# 100-678-02-00_CIB.net
KiCad netlist of a schematic drawn in Altium Designer
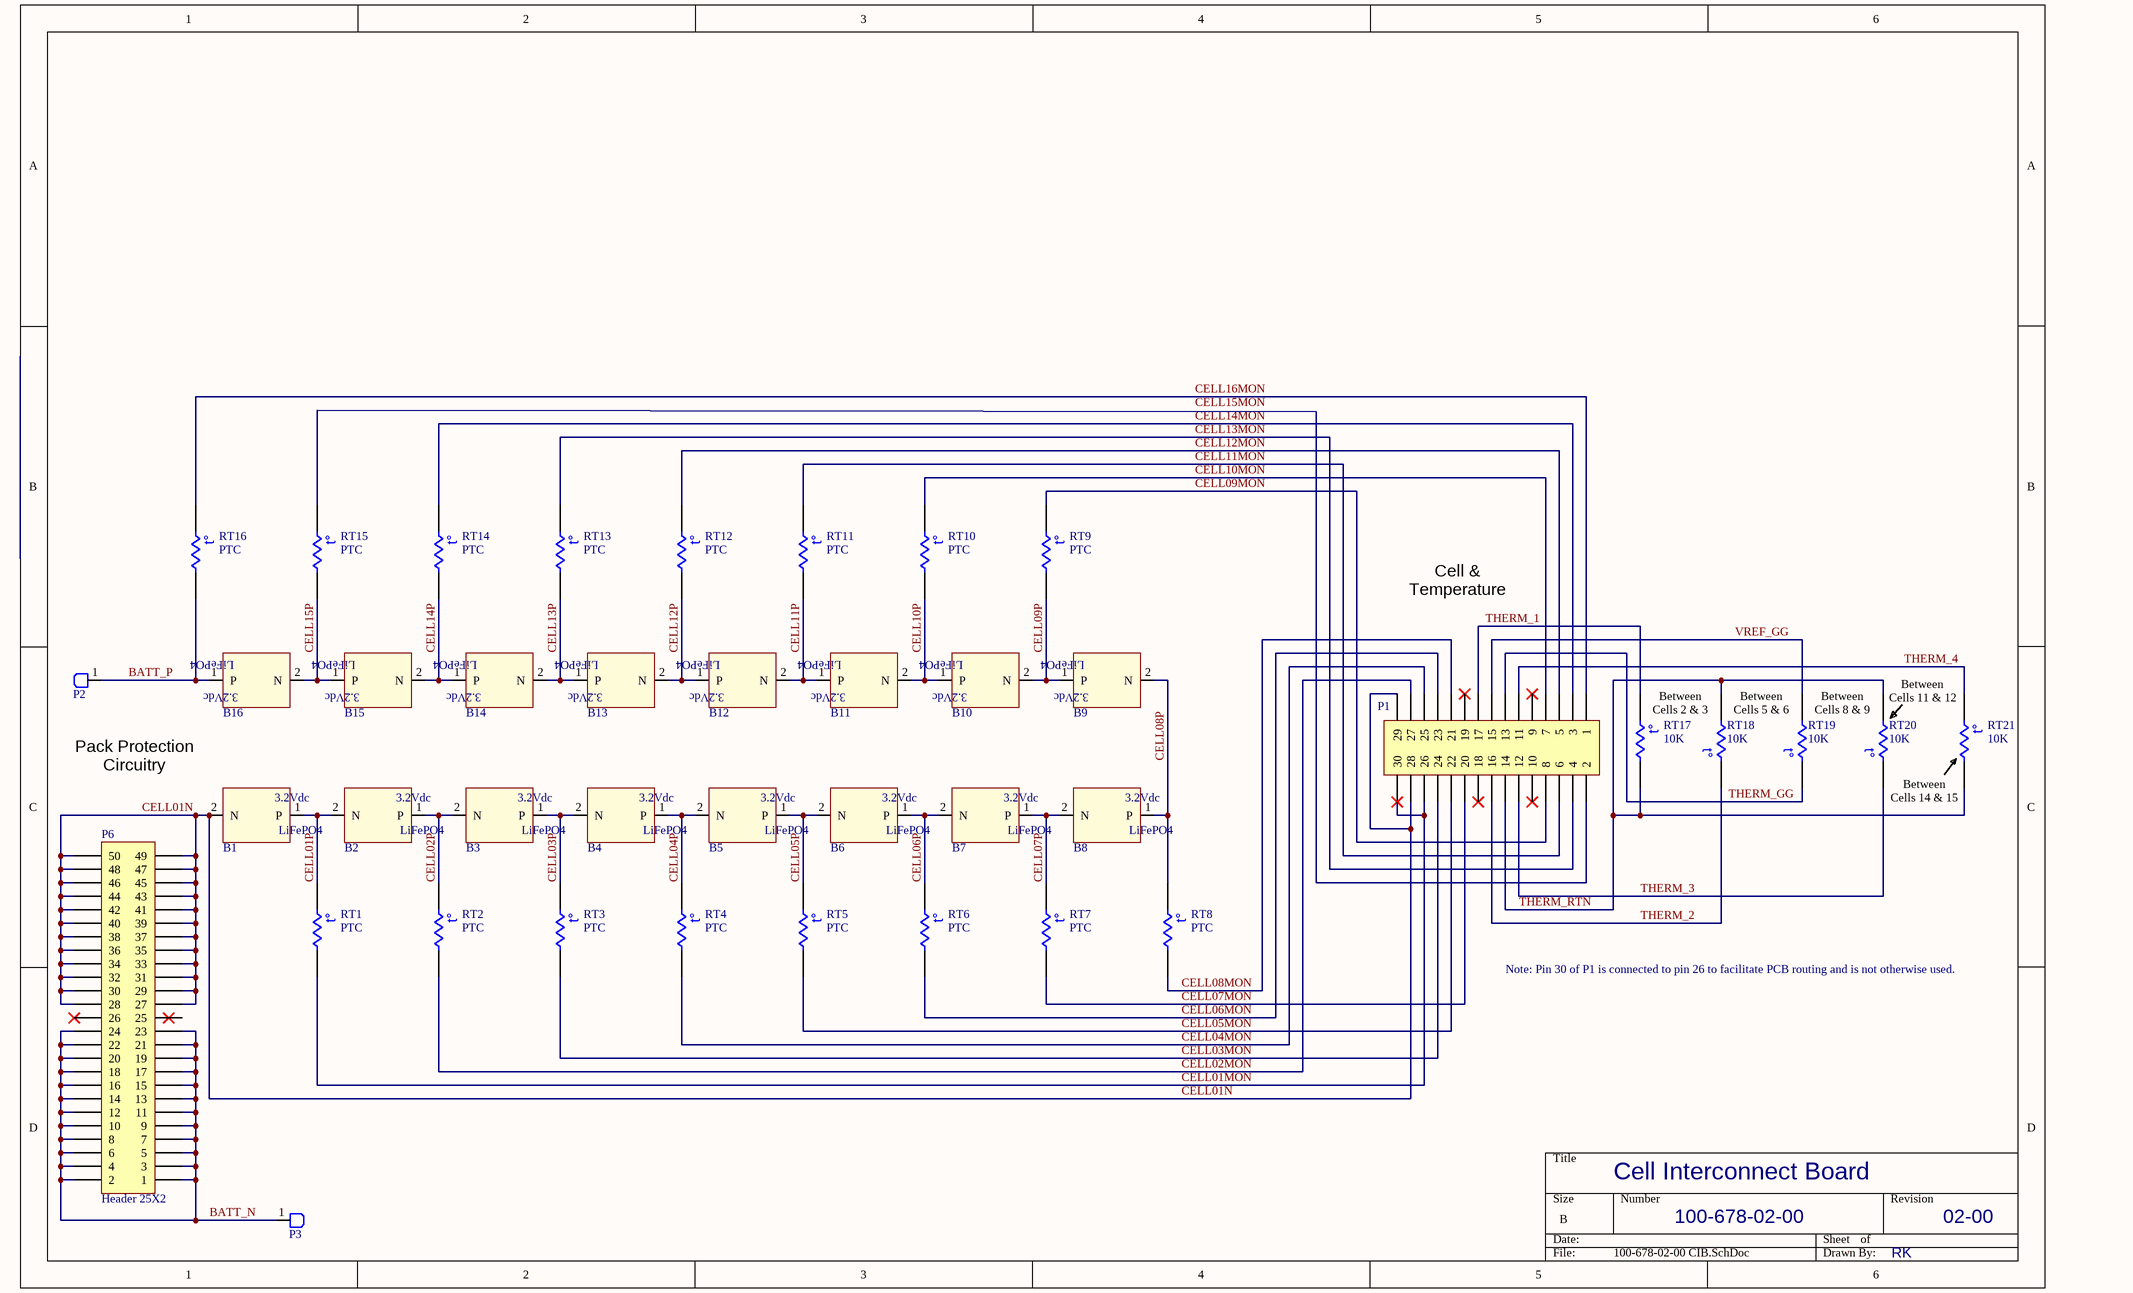
[diagram p0: 100-678-02-00 CIB.SchDoc]

(export (version "E")
  (design (tool "Eeschema 10.0.6"))
  (components
    (comp (ref "B1")
      (value "TENERGY 30209 LiFePO4 Cell")
      (footprint "TENERGY 30209 LiFePO4 Cell")
      (libsource (lib "") (part "TENERGY 30209 LiFePO4 Cell_1"))
    )
    (comp (ref "B2")
      (value "TENERGY 30209 LiFePO4 Cell")
      (footprint "TENERGY 30209 LiFePO4 Cell")
      (libsource (lib "") (part "TENERGY 30209 LiFePO4 Cell_1"))
    )
    (comp (ref "B3")
      (value "TENERGY 30209 LiFePO4 Cell")
      (footprint "TENERGY 30209 LiFePO4 Cell")
      (libsource (lib "") (part "TENERGY 30209 LiFePO4 Cell_1"))
    )
    (comp (ref "B4")
      (value "TENERGY 30209 LiFePO4 Cell")
      (footprint "TENERGY 30209 LiFePO4 Cell")
      (libsource (lib "") (part "TENERGY 30209 LiFePO4 Cell_1"))
    )
    (comp (ref "B5")
      (value "TENERGY 30209 LiFePO4 Cell")
      (footprint "TENERGY 30209 LiFePO4 Cell")
      (libsource (lib "") (part "TENERGY 30209 LiFePO4 Cell_1"))
    )
    (comp (ref "B6")
      (value "TENERGY 30209 LiFePO4 Cell")
      (footprint "TENERGY 30209 LiFePO4 Cell")
      (libsource (lib "") (part "TENERGY 30209 LiFePO4 Cell_1"))
    )
    (comp (ref "B7")
      (value "TENERGY 30209 LiFePO4 Cell")
      (footprint "TENERGY 30209 LiFePO4 Cell")
      (libsource (lib "") (part "TENERGY 30209 LiFePO4 Cell_1"))
    )
    (comp (ref "B8")
      (value "TENERGY 30209 LiFePO4 Cell")
      (footprint "TENERGY 30209 LiFePO4 Cell")
      (libsource (lib "") (part "TENERGY 30209 LiFePO4 Cell_1"))
    )
    (comp (ref "B9")
      (value "TENERGY 30209 LiFePO4 Cell")
      (footprint "TENERGY 30209 LiFePO4 Cell")
      (libsource (lib "STEM_SCH") (part "TENERGY 30209 LiFePO4 Cell"))
    )
    (comp (ref "B10")
      (value "TENERGY 30209 LiFePO4 Cell")
      (footprint "TENERGY 30209 LiFePO4 Cell")
      (libsource (lib "STEM_SCH") (part "TENERGY 30209 LiFePO4 Cell"))
    )
    (comp (ref "B11")
      (value "TENERGY 30209 LiFePO4 Cell")
      (footprint "TENERGY 30209 LiFePO4 Cell")
      (libsource (lib "STEM_SCH") (part "TENERGY 30209 LiFePO4 Cell"))
    )
    (comp (ref "B12")
      (value "TENERGY 30209 LiFePO4 Cell")
      (footprint "TENERGY 30209 LiFePO4 Cell")
      (libsource (lib "STEM_SCH") (part "TENERGY 30209 LiFePO4 Cell"))
    )
    (comp (ref "B13")
      (value "TENERGY 30209 LiFePO4 Cell")
      (footprint "TENERGY 30209 LiFePO4 Cell")
      (libsource (lib "STEM_SCH") (part "TENERGY 30209 LiFePO4 Cell"))
    )
    (comp (ref "B14")
      (value "TENERGY 30209 LiFePO4 Cell")
      (footprint "TENERGY 30209 LiFePO4 Cell")
      (libsource (lib "STEM_SCH") (part "TENERGY 30209 LiFePO4 Cell"))
    )
    (comp (ref "B15")
      (value "TENERGY 30209 LiFePO4 Cell")
      (footprint "TENERGY 30209 LiFePO4 Cell")
      (libsource (lib "STEM_SCH") (part "TENERGY 30209 LiFePO4 Cell"))
    )
    (comp (ref "B16")
      (value "TENERGY 30209 LiFePO4 Cell")
      (footprint "TENERGY 30209 LiFePO4 Cell")
      (libsource (lib "STEM_SCH") (part "TENERGY 30209 LiFePO4 Cell"))
    )
    (comp (ref "P1")
      (value "Header 15X2")
      (footprint "CONN 2X15 SKT TH")
      (description "CONN, SKT, 15 X 2, 0.1\" CTRS, TH, 0.435\" HEIGHT GOLD")
      (fields
        (field (name "MANUFACTURER") "SAMTEC")
        (field (name "MANUFACTURER PART NUMBER") "ESQ-115-13-L-D")
        (field (name "PUBLISHER") "Altium Limited")
      )
      (libsource (lib "Miscellaneous Connectors") (part "Header 15X2"))
    )
    (comp (ref "P2")
      (value "CONN TAB MALE 1/4\" PC TH")
      (footprint "TERM, LUG, RING TONGUE, #8-32 W/ PEM")
      (description "NUT PEM 8-32 0.25\" HOLE")
      (fields
        (field (name "MANUFACTURER") "PennEngineering")
        (field (name "MANUFACTURER PART NUMBER") "KFS2-832")
      )
      (libsource (lib "STEM_SCH") (part "CONN TAB MALE 1/4{dblquote} PC TH"))
    )
    (comp (ref "P3")
      (value "CONN TAB MALE 1/4\" PC TH")
      (footprint "TERM, LUG, RING TONGUE, #8-32 W/ PEM")
      (description "NUT PEM 8-32 0.25\" HOLE")
      (fields
        (field (name "MANUFACTURER") "PennEngineering")
        (field (name "MANUFACTURER PART NUMBER") "KFS2-832")
      )
      (libsource (lib "STEM_SCH") (part "CONN TAB MALE 1/4{dblquote} PC TH"))
    )
    (comp (ref "P6")
      (value "Header 25X2")
      (footprint "CONN 2X25 SKT TH")
      (description "CONN, SKT, 25 X 2, 0.1\" CTRS, TH, 0.435\" HEIGHT GOLD")
      (fields
        (field (name "MANUFACTURER") "SAMTEC")
        (field (name "MANUFACTURER PART NUMBER") "ESQ-125-13-L-D")
        (field (name "PUBLISHER") "Altium Limited")
      )
      (libsource (lib "Miscellaneous Connectors") (part "Header 25X2"))
    )
    (comp (ref "RT1")
      (value "PTC")
      (footprint "THERM 1812")
      (description "PTC 2.00A 8VDC RESETTABLE 1812L")
      (fields
        (field (name "MANUFACTURER") "Littelfuse Inc")
        (field (name "MANUFACTURER PART NUMBER") "1812L200THPR")
      )
      (libsource (lib "Miscellaneous Devices") (part "Res Thermal"))
    )
    (comp (ref "RT2")
      (value "PTC")
      (footprint "THERM 1812")
      (description "PTC 2.00A 8VDC RESETTABLE 1812L")
      (fields
        (field (name "MANUFACTURER") "Littelfuse Inc")
        (field (name "MANUFACTURER PART NUMBER") "1812L200THPR")
      )
      (libsource (lib "Miscellaneous Devices") (part "Res Thermal"))
    )
    (comp (ref "RT3")
      (value "PTC")
      (footprint "THERM 1812")
      (description "PTC 2.00A 8VDC RESETTABLE 1812L")
      (fields
        (field (name "MANUFACTURER") "Littelfuse Inc")
        (field (name "MANUFACTURER PART NUMBER") "1812L200THPR")
      )
      (libsource (lib "Miscellaneous Devices") (part "Res Thermal"))
    )
    (comp (ref "RT4")
      (value "PTC")
      (footprint "THERM 1812")
      (description "PTC 2.00A 8VDC RESETTABLE 1812L")
      (fields
        (field (name "MANUFACTURER") "Littelfuse Inc")
        (field (name "MANUFACTURER PART NUMBER") "1812L200THPR")
      )
      (libsource (lib "Miscellaneous Devices") (part "Res Thermal"))
    )
    (comp (ref "RT5")
      (value "PTC")
      (footprint "THERM 1812")
      (description "PTC 2.00A 8VDC RESETTABLE 1812L")
      (fields
        (field (name "MANUFACTURER") "Littelfuse Inc")
        (field (name "MANUFACTURER PART NUMBER") "1812L200THPR")
      )
      (libsource (lib "Miscellaneous Devices") (part "Res Thermal"))
    )
    (comp (ref "RT6")
      (value "PTC")
      (footprint "THERM 1812")
      (description "PTC 2.00A 8VDC RESETTABLE 1812L")
      (fields
        (field (name "MANUFACTURER") "Littelfuse Inc")
        (field (name "MANUFACTURER PART NUMBER") "1812L200THPR")
      )
      (libsource (lib "Miscellaneous Devices") (part "Res Thermal"))
    )
    (comp (ref "RT7")
      (value "PTC")
      (footprint "THERM 1812")
      (description "PTC 2.00A 8VDC RESETTABLE 1812L")
      (fields
        (field (name "MANUFACTURER") "Littelfuse Inc")
        (field (name "MANUFACTURER PART NUMBER") "1812L200THPR")
      )
      (libsource (lib "Miscellaneous Devices") (part "Res Thermal"))
    )
    (comp (ref "RT8")
      (value "PTC")
      (footprint "THERM 1812")
      (description "PTC 2.00A 8VDC RESETTABLE 1812L")
      (fields
        (field (name "MANUFACTURER") "Littelfuse Inc")
        (field (name "MANUFACTURER PART NUMBER") "1812L200THPR")
      )
      (libsource (lib "Miscellaneous Devices") (part "Res Thermal"))
    )
    (comp (ref "RT9")
      (value "PTC")
      (footprint "THERM 1812")
      (description "PTC 2.00A 8VDC RESETTABLE 1812L")
      (fields
        (field (name "MANUFACTURER") "Littelfuse Inc")
        (field (name "MANUFACTURER PART NUMBER") "1812L200THPR")
      )
      (libsource (lib "Miscellaneous Devices") (part "Res Thermal"))
    )
    (comp (ref "RT10")
      (value "PTC")
      (footprint "THERM 1812")
      (description "PTC 2.00A 8VDC RESETTABLE 1812L")
      (fields
        (field (name "MANUFACTURER") "Littelfuse Inc")
        (field (name "MANUFACTURER PART NUMBER") "1812L200THPR")
      )
      (libsource (lib "Miscellaneous Devices") (part "Res Thermal"))
    )
    (comp (ref "RT11")
      (value "PTC")
      (footprint "THERM 1812")
      (description "PTC 2.00A 8VDC RESETTABLE 1812L")
      (fields
        (field (name "MANUFACTURER") "Littelfuse Inc")
        (field (name "MANUFACTURER PART NUMBER") "1812L200THPR")
      )
      (libsource (lib "Miscellaneous Devices") (part "Res Thermal"))
    )
    (comp (ref "RT12")
      (value "PTC")
      (footprint "THERM 1812")
      (description "PTC 2.00A 8VDC RESETTABLE 1812L")
      (fields
        (field (name "MANUFACTURER") "Littelfuse Inc")
        (field (name "MANUFACTURER PART NUMBER") "1812L200THPR")
      )
      (libsource (lib "Miscellaneous Devices") (part "Res Thermal"))
    )
    (comp (ref "RT13")
      (value "PTC")
      (footprint "THERM 1812")
      (description "PTC 2.00A 8VDC RESETTABLE 1812L")
      (fields
        (field (name "MANUFACTURER") "Littelfuse Inc")
        (field (name "MANUFACTURER PART NUMBER") "1812L200THPR")
      )
      (libsource (lib "Miscellaneous Devices") (part "Res Thermal"))
    )
    (comp (ref "RT14")
      (value "PTC")
      (footprint "THERM 1812")
      (description "PTC 2.00A 8VDC RESETTABLE 1812L")
      (fields
        (field (name "MANUFACTURER") "Littelfuse Inc")
        (field (name "MANUFACTURER PART NUMBER") "1812L200THPR")
      )
      (libsource (lib "Miscellaneous Devices") (part "Res Thermal"))
    )
    (comp (ref "RT15")
      (value "PTC")
      (footprint "THERM 1812")
      (description "PTC 2.00A 8VDC RESETTABLE 1812L")
      (fields
        (field (name "MANUFACTURER") "Littelfuse Inc")
        (field (name "MANUFACTURER PART NUMBER") "1812L200THPR")
      )
      (libsource (lib "Miscellaneous Devices") (part "Res Thermal"))
    )
    (comp (ref "RT16")
      (value "PTC")
      (footprint "THERM 1812")
      (description "PTC 2.00A 8VDC RESETTABLE 1812L")
      (fields
        (field (name "MANUFACTURER") "Littelfuse Inc")
        (field (name "MANUFACTURER PART NUMBER") "1812L200THPR")
      )
      (libsource (lib "Miscellaneous Devices") (part "Res Thermal"))
    )
    (comp (ref "RT17")
      (value "10K")
      (footprint "THERMISTOR JT")
      (description "THERMISTOR NTC 10K B3435 TF 100MM")
      (fields (field (name "MANUFACTURER PART NUMBER") "103JT-100") (field (name "MANUFACTURER") "Semitec"))
      (libsource (lib "Miscellaneous Devices") (part "Res Thermal"))
    )
    (comp (ref "RT18")
      (value "10K")
      (footprint "THERMISTOR JT")
      (description "THERMISTOR NTC 10K B3435 TF 100MM")
      (fields (field (name "MANUFACTURER PART NUMBER") "103JT-100") (field (name "MANUFACTURER") "Semitec"))
      (libsource (lib "Miscellaneous Devices") (part "Res Thermal"))
    )
    (comp (ref "RT19")
      (value "10K")
      (footprint "THERMISTOR JT")
      (description "THERMISTOR NTC 10K B3435 TF 100MM")
      (fields (field (name "MANUFACTURER PART NUMBER") "103JT-100") (field (name "MANUFACTURER") "Semitec"))
      (libsource (lib "Miscellaneous Devices") (part "Res Thermal"))
    )
    (comp (ref "RT20")
      (value "10K")
      (footprint "THERMISTOR JT")
      (description "THERMISTOR NTC 10K B3435 TF 100MM")
      (fields (field (name "MANUFACTURER PART NUMBER") "103JT-100") (field (name "MANUFACTURER") "Semitec"))
      (libsource (lib "Miscellaneous Devices") (part "Res Thermal"))
    )
    (comp (ref "RT21")
      (value "10K")
      (footprint "THERMISTOR JT")
      (description "THERMISTOR NTC 10K B3435 TF 100MM")
      (fields (field (name "MANUFACTURER PART NUMBER") "103JT-100") (field (name "MANUFACTURER") "Semitec"))
      (libsource (lib "Miscellaneous Devices") (part "Res Thermal"))
    )
  )
  (nets
    (net (code "1") (name "/BATT_N") (class "Default")
      (node (ref "P3") (pin "1") (pinfunction "1_1") (pintype "passive"))
      (node (ref "P6") (pin "1") (pinfunction "1_1") (pintype "passive"))
      (node (ref "P6") (pin "10") (pinfunction "10_10") (pintype "passive"))
      (node (ref "P6") (pin "11") (pinfunction "11_11") (pintype "passive"))
      (node (ref "P6") (pin "12") (pinfunction "12_12") (pintype "passive"))
      (node (ref "P6") (pin "13") (pinfunction "13_13") (pintype "passive"))
      (node (ref "P6") (pin "14") (pinfunction "14_14") (pintype "passive"))
      (node (ref "P6") (pin "15") (pinfunction "15_15") (pintype "passive"))
      (node (ref "P6") (pin "16") (pinfunction "16_16") (pintype "passive"))
      (node (ref "P6") (pin "17") (pinfunction "17_17") (pintype "passive"))
      (node (ref "P6") (pin "18") (pinfunction "18_18") (pintype "passive"))
      (node (ref "P6") (pin "19") (pinfunction "19_19") (pintype "passive"))
      (node (ref "P6") (pin "2") (pinfunction "2_2") (pintype "passive"))
      (node (ref "P6") (pin "20") (pinfunction "20_20") (pintype "passive"))
      (node (ref "P6") (pin "21") (pinfunction "21_21") (pintype "passive"))
      (node (ref "P6") (pin "22") (pinfunction "22_22") (pintype "passive"))
      (node (ref "P6") (pin "23") (pinfunction "23_23") (pintype "passive"))
      (node (ref "P6") (pin "24") (pinfunction "24_24") (pintype "passive"))
      (node (ref "P6") (pin "3") (pinfunction "3_3") (pintype "passive"))
      (node (ref "P6") (pin "4") (pinfunction "4_4") (pintype "passive"))
      (node (ref "P6") (pin "5") (pinfunction "5_5") (pintype "passive"))
      (node (ref "P6") (pin "6") (pinfunction "6_6") (pintype "passive"))
      (node (ref "P6") (pin "7") (pinfunction "7_7") (pintype "passive"))
      (node (ref "P6") (pin "8") (pinfunction "8_8") (pintype "passive"))
      (node (ref "P6") (pin "9") (pinfunction "9_9") (pintype "passive"))
    )
    (net (code "2") (name "/BATT_P") (class "Default")
      (node (ref "B16") (pin "1") (pinfunction "P_1") (pintype "passive"))
      (node (ref "P2") (pin "1") (pinfunction "1_1") (pintype "passive"))
      (node (ref "RT16") (pin "2") (pinfunction "2_2") (pintype "passive"))
    )
    (net (code "3") (name "/CELL01MON") (class "Default")
      (node (ref "P1") (pin "26") (pinfunction "26_26") (pintype "passive"))
      (node (ref "P1") (pin "30") (pinfunction "30_30") (pintype "passive"))
      (node (ref "RT1") (pin "2") (pinfunction "2_2") (pintype "passive"))
    )
    (net (code "4") (name "/CELL01N") (class "Default")
      (node (ref "B1") (pin "2") (pinfunction "N_2") (pintype "passive"))
      (node (ref "P1") (pin "28") (pinfunction "28_28") (pintype "passive"))
      (node (ref "P1") (pin "29") (pinfunction "29_29") (pintype "passive"))
      (node (ref "P6") (pin "27") (pinfunction "27_27") (pintype "passive"))
      (node (ref "P6") (pin "28") (pinfunction "28_28") (pintype "passive"))
      (node (ref "P6") (pin "29") (pinfunction "29_29") (pintype "passive"))
      (node (ref "P6") (pin "30") (pinfunction "30_30") (pintype "passive"))
      (node (ref "P6") (pin "31") (pinfunction "31_31") (pintype "passive"))
      (node (ref "P6") (pin "32") (pinfunction "32_32") (pintype "passive"))
      (node (ref "P6") (pin "33") (pinfunction "33_33") (pintype "passive"))
      (node (ref "P6") (pin "34") (pinfunction "34_34") (pintype "passive"))
      (node (ref "P6") (pin "35") (pinfunction "35_35") (pintype "passive"))
      (node (ref "P6") (pin "36") (pinfunction "36_36") (pintype "passive"))
      (node (ref "P6") (pin "37") (pinfunction "37_37") (pintype "passive"))
      (node (ref "P6") (pin "38") (pinfunction "38_38") (pintype "passive"))
      (node (ref "P6") (pin "39") (pinfunction "39_39") (pintype "passive"))
      (node (ref "P6") (pin "40") (pinfunction "40_40") (pintype "passive"))
      (node (ref "P6") (pin "41") (pinfunction "41_41") (pintype "passive"))
      (node (ref "P6") (pin "42") (pinfunction "42_42") (pintype "passive"))
      (node (ref "P6") (pin "43") (pinfunction "43_43") (pintype "passive"))
      (node (ref "P6") (pin "44") (pinfunction "44_44") (pintype "passive"))
      (node (ref "P6") (pin "45") (pinfunction "45_45") (pintype "passive"))
      (node (ref "P6") (pin "46") (pinfunction "46_46") (pintype "passive"))
      (node (ref "P6") (pin "47") (pinfunction "47_47") (pintype "passive"))
      (node (ref "P6") (pin "48") (pinfunction "48_48") (pintype "passive"))
      (node (ref "P6") (pin "49") (pinfunction "49_49") (pintype "passive"))
      (node (ref "P6") (pin "50") (pinfunction "50_50") (pintype "passive"))
    )
    (net (code "5") (name "/CELL01P") (class "Default")
      (node (ref "B1") (pin "1") (pinfunction "P_1") (pintype "passive"))
      (node (ref "B2") (pin "2") (pinfunction "N_2") (pintype "passive"))
      (node (ref "RT1") (pin "1") (pinfunction "1_1") (pintype "passive"))
    )
    (net (code "6") (name "/CELL02MON") (class "Default")
      (node (ref "P1") (pin "27") (pinfunction "27_27") (pintype "passive"))
      (node (ref "RT2") (pin "2") (pinfunction "2_2") (pintype "passive"))
    )
    (net (code "7") (name "/CELL02P") (class "Default")
      (node (ref "B2") (pin "1") (pinfunction "P_1") (pintype "passive"))
      (node (ref "B3") (pin "2") (pinfunction "N_2") (pintype "passive"))
      (node (ref "RT2") (pin "1") (pinfunction "1_1") (pintype "passive"))
    )
    (net (code "8") (name "/CELL03MON") (class "Default")
      (node (ref "P1") (pin "24") (pinfunction "24_24") (pintype "passive"))
      (node (ref "RT3") (pin "2") (pinfunction "2_2") (pintype "passive"))
    )
    (net (code "9") (name "/CELL03P") (class "Default")
      (node (ref "B3") (pin "1") (pinfunction "P_1") (pintype "passive"))
      (node (ref "B4") (pin "2") (pinfunction "N_2") (pintype "passive"))
      (node (ref "RT3") (pin "1") (pinfunction "1_1") (pintype "passive"))
    )
    (net (code "10") (name "/CELL04MON") (class "Default")
      (node (ref "P1") (pin "25") (pinfunction "25_25") (pintype "passive"))
      (node (ref "RT4") (pin "2") (pinfunction "2_2") (pintype "passive"))
    )
    (net (code "11") (name "/CELL04P") (class "Default")
      (node (ref "B4") (pin "1") (pinfunction "P_1") (pintype "passive"))
      (node (ref "B5") (pin "2") (pinfunction "N_2") (pintype "passive"))
      (node (ref "RT4") (pin "1") (pinfunction "1_1") (pintype "passive"))
    )
    (net (code "12") (name "/CELL05MON") (class "Default")
      (node (ref "P1") (pin "22") (pinfunction "22_22") (pintype "passive"))
      (node (ref "RT5") (pin "2") (pinfunction "2_2") (pintype "passive"))
    )
    (net (code "13") (name "/CELL05P") (class "Default")
      (node (ref "B5") (pin "1") (pinfunction "P_1") (pintype "passive"))
      (node (ref "B6") (pin "2") (pinfunction "N_2") (pintype "passive"))
      (node (ref "RT5") (pin "1") (pinfunction "1_1") (pintype "passive"))
    )
    (net (code "14") (name "/CELL06MON") (class "Default")
      (node (ref "P1") (pin "23") (pinfunction "23_23") (pintype "passive"))
      (node (ref "RT6") (pin "2") (pinfunction "2_2") (pintype "passive"))
    )
    (net (code "15") (name "/CELL06P") (class "Default")
      (node (ref "B6") (pin "1") (pinfunction "P_1") (pintype "passive"))
      (node (ref "B7") (pin "2") (pinfunction "N_2") (pintype "passive"))
      (node (ref "RT6") (pin "1") (pinfunction "1_1") (pintype "passive"))
    )
    (net (code "16") (name "/CELL07MON") (class "Default")
      (node (ref "P1") (pin "20") (pinfunction "20_20") (pintype "passive"))
      (node (ref "RT7") (pin "2") (pinfunction "2_2") (pintype "passive"))
    )
    (net (code "17") (name "/CELL07P") (class "Default")
      (node (ref "B7") (pin "1") (pinfunction "P_1") (pintype "passive"))
      (node (ref "B8") (pin "2") (pinfunction "N_2") (pintype "passive"))
      (node (ref "RT7") (pin "1") (pinfunction "1_1") (pintype "passive"))
    )
    (net (code "18") (name "/CELL08MON") (class "Default")
      (node (ref "P1") (pin "21") (pinfunction "21_21") (pintype "passive"))
      (node (ref "RT8") (pin "2") (pinfunction "2_2") (pintype "passive"))
    )
    (net (code "19") (name "/CELL08P") (class "Default")
      (node (ref "B8") (pin "1") (pinfunction "P_1") (pintype "passive"))
      (node (ref "B9") (pin "2") (pinfunction "N_2") (pintype "passive"))
      (node (ref "RT8") (pin "1") (pinfunction "1_1") (pintype "passive"))
    )
    (net (code "20") (name "/CELL09MON") (class "Default")
      (node (ref "P1") (pin "8") (pinfunction "8_8") (pintype "passive"))
      (node (ref "RT9") (pin "1") (pinfunction "1_1") (pintype "passive"))
    )
    (net (code "21") (name "/CELL09P") (class "Default")
      (node (ref "B10") (pin "2") (pinfunction "N_2") (pintype "passive"))
      (node (ref "B9") (pin "1") (pinfunction "P_1") (pintype "passive"))
      (node (ref "RT9") (pin "2") (pinfunction "2_2") (pintype "passive"))
    )
    (net (code "22") (name "/CELL10MON") (class "Default")
      (node (ref "P1") (pin "7") (pinfunction "7_7") (pintype "passive"))
      (node (ref "RT10") (pin "1") (pinfunction "1_1") (pintype "passive"))
    )
    (net (code "23") (name "/CELL10P") (class "Default")
      (node (ref "B10") (pin "1") (pinfunction "P_1") (pintype "passive"))
      (node (ref "B11") (pin "2") (pinfunction "N_2") (pintype "passive"))
      (node (ref "RT10") (pin "2") (pinfunction "2_2") (pintype "passive"))
    )
    (net (code "24") (name "/CELL11MON") (class "Default")
      (node (ref "P1") (pin "6") (pinfunction "6_6") (pintype "passive"))
      (node (ref "RT11") (pin "1") (pinfunction "1_1") (pintype "passive"))
    )
    (net (code "25") (name "/CELL11P") (class "Default")
      (node (ref "B11") (pin "1") (pinfunction "P_1") (pintype "passive"))
      (node (ref "B12") (pin "2") (pinfunction "N_2") (pintype "passive"))
      (node (ref "RT11") (pin "2") (pinfunction "2_2") (pintype "passive"))
    )
    (net (code "26") (name "/CELL12MON") (class "Default")
      (node (ref "P1") (pin "5") (pinfunction "5_5") (pintype "passive"))
      (node (ref "RT12") (pin "1") (pinfunction "1_1") (pintype "passive"))
    )
    (net (code "27") (name "/CELL12P") (class "Default")
      (node (ref "B12") (pin "1") (pinfunction "P_1") (pintype "passive"))
      (node (ref "B13") (pin "2") (pinfunction "N_2") (pintype "passive"))
      (node (ref "RT12") (pin "2") (pinfunction "2_2") (pintype "passive"))
    )
    (net (code "28") (name "/CELL13MON") (class "Default")
      (node (ref "P1") (pin "4") (pinfunction "4_4") (pintype "passive"))
      (node (ref "RT13") (pin "1") (pinfunction "1_1") (pintype "passive"))
    )
    (net (code "29") (name "/CELL13P") (class "Default")
      (node (ref "B13") (pin "1") (pinfunction "P_1") (pintype "passive"))
      (node (ref "B14") (pin "2") (pinfunction "N_2") (pintype "passive"))
      (node (ref "RT13") (pin "2") (pinfunction "2_2") (pintype "passive"))
    )
    (net (code "30") (name "/CELL14MON") (class "Default")
      (node (ref "P1") (pin "3") (pinfunction "3_3") (pintype "passive"))
      (node (ref "RT14") (pin "1") (pinfunction "1_1") (pintype "passive"))
    )
    (net (code "31") (name "/CELL14P") (class "Default")
      (node (ref "B14") (pin "1") (pinfunction "P_1") (pintype "passive"))
      (node (ref "B15") (pin "2") (pinfunction "N_2") (pintype "passive"))
      (node (ref "RT14") (pin "2") (pinfunction "2_2") (pintype "passive"))
    )
    (net (code "33") (name "/CELL15P") (class "Default")
      (node (ref "B15") (pin "1") (pinfunction "P_1") (pintype "passive"))
      (node (ref "B16") (pin "2") (pinfunction "N_2") (pintype "passive"))
      (node (ref "RT15") (pin "2") (pinfunction "2_2") (pintype "passive"))
    )
    (net (code "34") (name "/CELL16MON") (class "Default")
      (node (ref "P1") (pin "1") (pinfunction "1_1") (pintype "passive"))
      (node (ref "RT16") (pin "1") (pinfunction "1_1") (pintype "passive"))
    )
    (net (code "35") (name "/THERM_1") (class "Default")
      (node (ref "P1") (pin "17") (pinfunction "17_17") (pintype "passive"))
      (node (ref "RT17") (pin "1") (pinfunction "1_1") (pintype "passive"))
    )
    (net (code "36") (name "/THERM_2") (class "Default")
      (node (ref "P1") (pin "16") (pinfunction "16_16") (pintype "passive"))
      (node (ref "RT18") (pin "1") (pinfunction "1_1") (pintype "passive"))
    )
    (net (code "37") (name "/THERM_3") (class "Default")
      (node (ref "P1") (pin "12") (pinfunction "12_12") (pintype "passive"))
      (node (ref "RT20") (pin "1") (pinfunction "1_1") (pintype "passive"))
    )
    (net (code "38") (name "/THERM_4") (class "Default")
      (node (ref "P1") (pin "11") (pinfunction "11_11") (pintype "passive"))
      (node (ref "RT21") (pin "1") (pinfunction "1_1") (pintype "passive"))
    )
    (net (code "39") (name "/THERM_GG") (class "Default")
      (node (ref "P1") (pin "13") (pinfunction "13_13") (pintype "passive"))
      (node (ref "RT19") (pin "1") (pinfunction "1_1") (pintype "passive"))
    )
    (net (code "40") (name "/THERM_RTN") (class "Default")
      (node (ref "P1") (pin "14") (pinfunction "14_14") (pintype "passive"))
      (node (ref "RT17") (pin "2") (pinfunction "2_2") (pintype "passive"))
      (node (ref "RT18") (pin "2") (pinfunction "2_2") (pintype "passive"))
      (node (ref "RT20") (pin "2") (pinfunction "2_2") (pintype "passive"))
      (node (ref "RT21") (pin "2") (pinfunction "2_2") (pintype "passive"))
    )
    (net (code "41") (name "/VREF_GG") (class "Default")
      (node (ref "P1") (pin "15") (pinfunction "15_15") (pintype "passive"))
      (node (ref "RT19") (pin "2") (pinfunction "2_2") (pintype "passive"))
    )
    (net (code "42") (name "Net-(P1-Pad2)") (class "Default")
      (node (ref "P1") (pin "2") (pinfunction "2_2") (pintype "passive"))
      (node (ref "RT15") (pin "1") (pinfunction "1_1") (pintype "passive"))
    )
    (net (code "43") (name "unconnected-(P1-Pad9)") (class "Default")
      (node (ref "P1") (pin "9") (pinfunction "9_9") (pintype "passive+no_connect"))
    )
    (net (code "44") (name "unconnected-(P1-Pad10)") (class "Default")
      (node (ref "P1") (pin "10") (pinfunction "10_10") (pintype "passive+no_connect"))
    )
    (net (code "45") (name "unconnected-(P1-Pad18)") (class "Default")
      (node (ref "P1") (pin "18") (pinfunction "18_18") (pintype "passive+no_connect"))
    )
    (net (code "46") (name "unconnected-(P1-Pad19)") (class "Default")
      (node (ref "P1") (pin "19") (pinfunction "19_19") (pintype "passive+no_connect"))
    )
    (net (code "47") (name "unconnected-(P6-Pad25)") (class "Default")
      (node (ref "P6") (pin "25") (pinfunction "25_25") (pintype "passive"))
    )
    (net (code "48") (name "unconnected-(P6-Pad26)") (class "Default")
      (node (ref "P6") (pin "26") (pinfunction "26_26") (pintype "passive+no_connect"))
    )
  )
)
